# FLS_Start_A_Distribution.net
KiCad netlist of a schematic drawn in Altium Designer
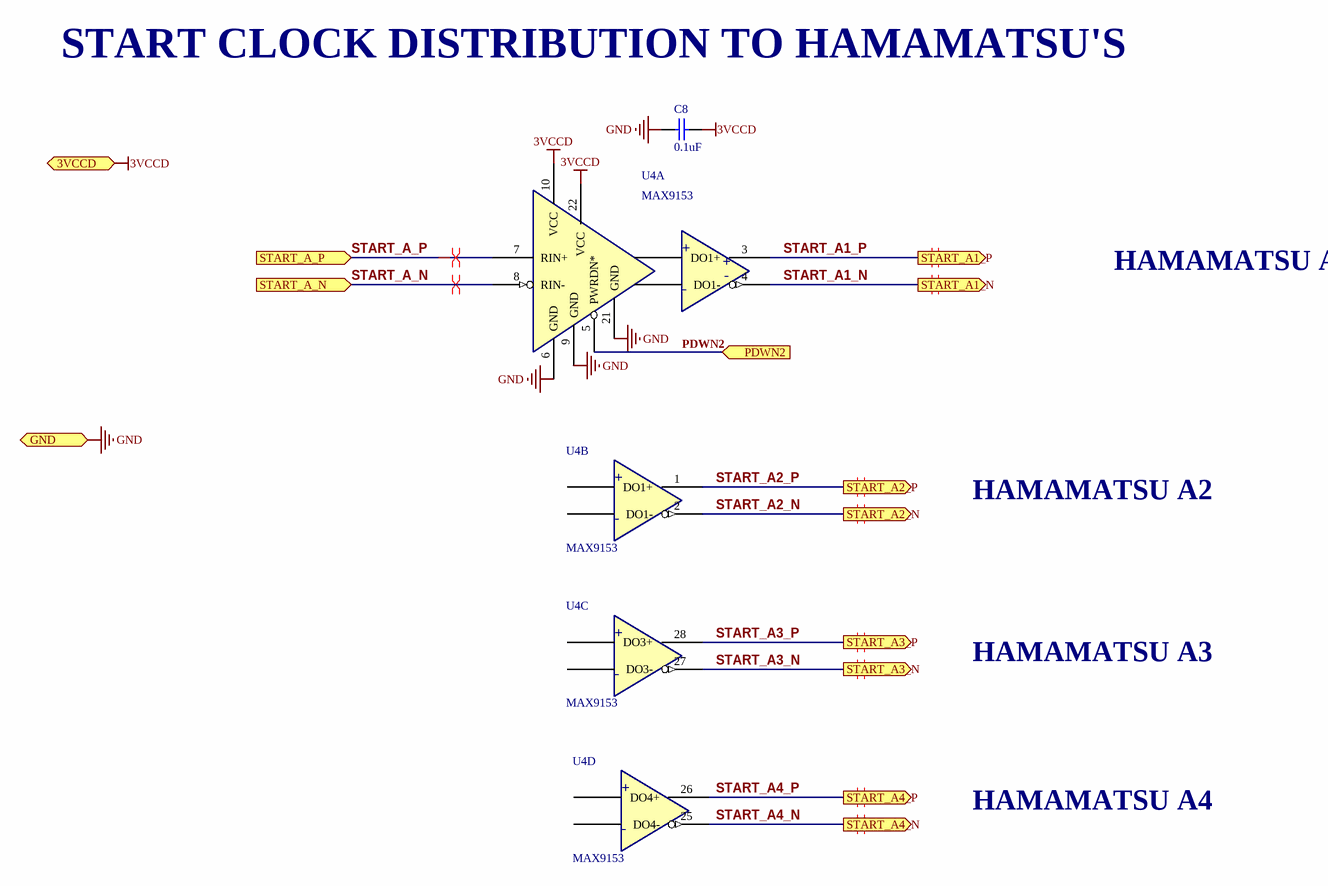
[diagram p0: FLS Start_A Distribution.SchDoc]

(export (version "E")
  (design (tool "Eeschema 10.0.6"))
  (components
    (comp (ref "C8")
      (value "0.1uF")
      (footprint "0805 slim")
      (description "Capacitor")
      (fields (field (name "PUBLISHER") "Altium Limited"))
      (libsource (lib "FLS ADC_A") (part "Cap"))
    )
    (comp (ref "U4")
      (value "MAX9153")
      (footprint "MAX9153EUI")
      (libsource (lib "FLS ADC_A") (part "MAX9153"))
    )
  )
  (nets
    (net (code "1") (name "/PDWN2") (class "Default")
      (node (ref "U4") (pin "5") (pinfunction "PWRDN*_5") (pintype "power_in"))
    )
    (net (code "2") (name "/START_A1_N") (class "Default")
      (node (ref "U4") (pin "4") (pinfunction "DO1-_4") (pintype "output"))
    )
    (net (code "3") (name "/START_A1_P") (class "Default")
      (node (ref "U4") (pin "3") (pinfunction "DO1+_3") (pintype "passive"))
    )
    (net (code "4") (name "/START_A2_N") (class "Default")
      (node (ref "U4") (pin "2") (pinfunction "DO1-_2") (pintype "output"))
    )
    (net (code "5") (name "/START_A2_P") (class "Default")
      (node (ref "U4") (pin "1") (pinfunction "DO1+_1") (pintype "passive"))
    )
    (net (code "6") (name "/START_A3_N") (class "Default")
      (node (ref "U4") (pin "27") (pinfunction "DO3-_27") (pintype "output"))
    )
    (net (code "7") (name "/START_A3_P") (class "Default")
      (node (ref "U4") (pin "28") (pinfunction "DO3+_28") (pintype "passive"))
    )
    (net (code "8") (name "/START_A4_N") (class "Default")
      (node (ref "U4") (pin "25") (pinfunction "DO4-_25") (pintype "output"))
    )
    (net (code "9") (name "/START_A4_P") (class "Default")
      (node (ref "U4") (pin "26") (pinfunction "DO4+_26") (pintype "passive"))
    )
    (net (code "10") (name "/START_A_N") (class "Default")
      (node (ref "U4") (pin "8") (pinfunction "RIN-_8") (pintype "input"))
    )
    (net (code "11") (name "/START_A_P") (class "Default")
      (node (ref "U4") (pin "7") (pinfunction "RIN+_7") (pintype "passive"))
    )
    (net (code "12") (name "3VCCD") (class "Default")
      (node (ref "C8") (pin "2") (pinfunction "2_2") (pintype "passive"))
      (node (ref "U4") (pin "10") (pinfunction "VCC_10") (pintype "power_in"))
      (node (ref "U4") (pin "22") (pinfunction "VCC_22") (pintype "power_in"))
    )
    (net (code "13") (name "GND") (class "Default")
      (node (ref "C8") (pin "1") (pinfunction "1_1") (pintype "passive"))
      (node (ref "U4") (pin "21") (pinfunction "GND_21") (pintype "power_in"))
      (node (ref "U4") (pin "6") (pinfunction "GND_6") (pintype "power_in"))
      (node (ref "U4") (pin "9") (pinfunction "GND_9") (pintype "power_in"))
    )
  )
)
